# Relay_switcher.net
KiCad netlist of a schematic drawn in Altium Designer
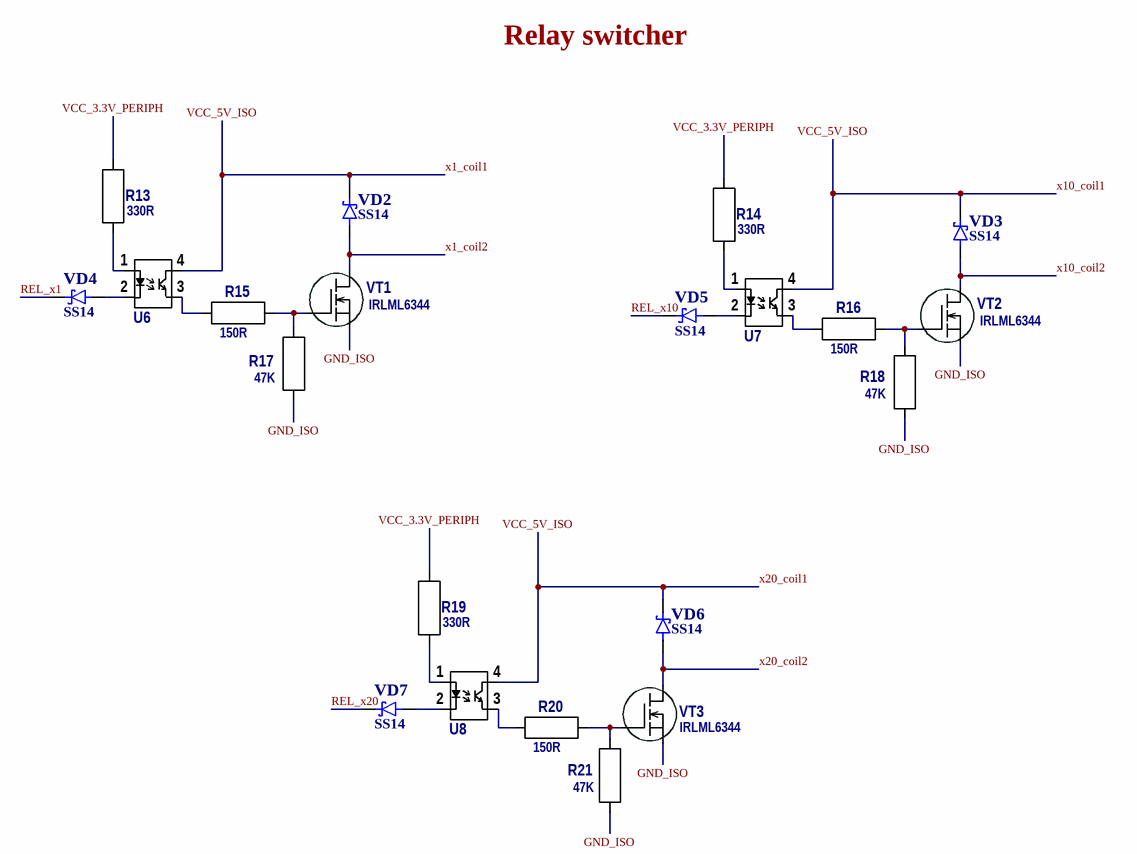
[diagram p0: Relay_switcher.SchDoc]

(export (version "E")
  (design (tool "Eeschema 10.0.6"))
  (components
    (comp (ref "R13") (value "330R") (footprint "Res_1206 3D") (libsource (lib "RLC V7.1_BVI") (part "R")))
    (comp (ref "R14") (value "330R") (footprint "Res_1206 3D") (libsource (lib "RLC V7.1_BVI") (part "R")))
    (comp (ref "R15") (value "150R") (footprint "Res_1206 3D") (libsource (lib "RLC V7.1_BVI") (part "R")))
    (comp (ref "R16") (value "150R") (footprint "Res_1206 3D") (libsource (lib "RLC V7.1_BVI") (part "R")))
    (comp (ref "R17") (value "47K") (footprint "Res_1206 3D") (libsource (lib "RLC V7.1_BVI") (part "R")))
    (comp (ref "R18") (value "47K") (footprint "Res_1206 3D") (libsource (lib "RLC V7.1_BVI") (part "R")))
    (comp (ref "R19") (value "330R") (footprint "Res_1206 3D") (libsource (lib "RLC V7.1_BVI") (part "R")))
    (comp (ref "R20") (value "150R") (footprint "Res_1206 3D") (libsource (lib "RLC V7.1_BVI") (part "R")))
    (comp (ref "R21") (value "47K") (footprint "Res_1206 3D") (libsource (lib "RLC V7.1_BVI") (part "R")))
    (comp (ref "U6")
      (value "Optocoupler EL817 DIP-4")
      (footprint "DIP-4")
      (description "Оптрон выход - транзистор")
      (libsource (lib "Optocoupler V2.2_BVI") (part "EL817"))
    )
    (comp (ref "U7")
      (value "Optocoupler EL817 DIP-4")
      (footprint "DIP-4")
      (description "Оптрон выход - транзистор")
      (libsource (lib "Optocoupler V2.2_BVI") (part "EL817"))
    )
    (comp (ref "U8")
      (value "Optocoupler EL817 DIP-4")
      (footprint "DIP-4")
      (description "Оптрон выход - транзистор")
      (libsource (lib "Optocoupler V2.2_BVI") (part "EL817"))
    )
    (comp (ref "VD2")
      (value "SS14")
      (footprint "SMA")
      (description "Diode Schottky 40 V 1A Surface Mount DO-214AC (SMA)")
      (fields (field (name "MF") "ON"))
      (libsource (lib "SS14") (part "SS14"))
    )
    (comp (ref "VD3")
      (value "SS14")
      (footprint "SMA")
      (description "Diode Schottky 40 V 1A Surface Mount DO-214AC (SMA)")
      (fields (field (name "MF") "ON"))
      (libsource (lib "SS14") (part "SS14"))
    )
    (comp (ref "VD4")
      (value "SS14")
      (footprint "SMA")
      (description "Diode Schottky 40 V 1A Surface Mount DO-214AC (SMA)")
      (fields (field (name "MF") "ON"))
      (libsource (lib "SS14") (part "SS14"))
    )
    (comp (ref "VD5")
      (value "SS14")
      (footprint "SMA")
      (description "Diode Schottky 40 V 1A Surface Mount DO-214AC (SMA)")
      (fields (field (name "MF") "ON"))
      (libsource (lib "SS14") (part "SS14"))
    )
    (comp (ref "VD6")
      (value "SS14")
      (footprint "SMA")
      (description "Diode Schottky 40 V 1A Surface Mount DO-214AC (SMA)")
      (fields (field (name "MF") "ON"))
      (libsource (lib "SS14") (part "SS14"))
    )
    (comp (ref "VD7")
      (value "SS14")
      (footprint "SMA")
      (description "Diode Schottky 40 V 1A Surface Mount DO-214AC (SMA)")
      (fields (field (name "MF") "ON"))
      (libsource (lib "SS14") (part "SS14"))
    )
    (comp (ref "VT1")
      (value "IRLML6344")
      (footprint "SOT-23-3")
      (description "Транзистор MOSFET N-канал IRLML6344")
      (libsource (lib "VD_VT_V6.3 BVI") (part "VT MOSFET-N"))
    )
    (comp (ref "VT2")
      (value "IRLML6344")
      (footprint "SOT-23-3")
      (description "Транзистор MOSFET N-канал IRLML6344")
      (libsource (lib "VD_VT_V6.3 BVI") (part "VT MOSFET-N"))
    )
    (comp (ref "VT3")
      (value "IRLML6344")
      (footprint "SOT-23-3")
      (description "Транзистор MOSFET N-канал IRLML6344")
      (libsource (lib "VD_VT_V6.3 BVI") (part "VT MOSFET-N"))
    )
  )
  (nets
    (net (code "1") (name "/GND_ISO") (class "Default")
      (node (ref "R17") (pin "2") (pintype "passive"))
      (node (ref "R18") (pin "2") (pintype "passive"))
      (node (ref "R21") (pin "2") (pintype "passive"))
      (node (ref "VT1") (pin "3") (pinfunction "S_3") (pintype "passive"))
      (node (ref "VT2") (pin "3") (pinfunction "S_3") (pintype "passive"))
      (node (ref "VT3") (pin "3") (pinfunction "S_3") (pintype "passive"))
    )
    (net (code "2") (name "/REL_x1") (class "Default")
      (node (ref "VD4") (pin "P2") (pinfunction "C_P2") (pintype "passive"))
    )
    (net (code "3") (name "/REL_x10") (class "Default")
      (node (ref "VD5") (pin "P2") (pinfunction "C_P2") (pintype "passive"))
    )
    (net (code "4") (name "/REL_x20") (class "Default")
      (node (ref "VD7") (pin "P2") (pinfunction "C_P2") (pintype "passive"))
    )
    (net (code "5") (name "/VCC_3.3V_PERIPH") (class "Default")
      (node (ref "R13") (pin "2") (pintype "passive"))
      (node (ref "R14") (pin "2") (pintype "passive"))
      (node (ref "R19") (pin "2") (pintype "passive"))
    )
    (net (code "6") (name "/VCC_5V_ISO") (class "Default")
      (node (ref "U6") (pin "4") (pinfunction "C_4") (pintype "passive"))
      (node (ref "U7") (pin "4") (pinfunction "C_4") (pintype "passive"))
      (node (ref "U8") (pin "4") (pinfunction "C_4") (pintype "passive"))
      (node (ref "VD2") (pin "P2") (pinfunction "C_P2") (pintype "passive"))
      (node (ref "VD3") (pin "P2") (pinfunction "C_P2") (pintype "passive"))
      (node (ref "VD6") (pin "P2") (pinfunction "C_P2") (pintype "passive"))
    )
    (net (code "7") (name "/x1_coil2") (class "Default")
      (node (ref "VD2") (pin "P1") (pinfunction "A_P1") (pintype "passive"))
      (node (ref "VT1") (pin "2") (pinfunction "D_2") (pintype "passive"))
    )
    (net (code "8") (name "/x10_coil2") (class "Default")
      (node (ref "VD3") (pin "P1") (pinfunction "A_P1") (pintype "passive"))
      (node (ref "VT2") (pin "2") (pinfunction "D_2") (pintype "passive"))
    )
    (net (code "9") (name "/x20_coil2") (class "Default")
      (node (ref "VD6") (pin "P1") (pinfunction "A_P1") (pintype "passive"))
      (node (ref "VT3") (pin "2") (pinfunction "D_2") (pintype "passive"))
    )
    (net (code "10") (name "Net-(U6-E)") (class "Default")
      (node (ref "R15") (pin "1") (pintype "passive"))
      (node (ref "U6") (pin "3") (pinfunction "E_3") (pintype "passive"))
    )
    (net (code "11") (name "Net-(U6-Led_A)") (class "Default")
      (node (ref "R13") (pin "1") (pintype "passive"))
      (node (ref "U6") (pin "1") (pinfunction "Led_A_1") (pintype "passive"))
    )
    (net (code "12") (name "Net-(U6-Led_C)") (class "Default")
      (node (ref "U6") (pin "2") (pinfunction "Led_C_2") (pintype "passive"))
      (node (ref "VD4") (pin "P1") (pinfunction "A_P1") (pintype "passive"))
    )
    (net (code "13") (name "Net-(U7-E)") (class "Default")
      (node (ref "R16") (pin "1") (pintype "passive"))
      (node (ref "U7") (pin "3") (pinfunction "E_3") (pintype "passive"))
    )
    (net (code "14") (name "Net-(U7-Led_A)") (class "Default")
      (node (ref "R14") (pin "1") (pintype "passive"))
      (node (ref "U7") (pin "1") (pinfunction "Led_A_1") (pintype "passive"))
    )
    (net (code "15") (name "Net-(U7-Led_C)") (class "Default")
      (node (ref "U7") (pin "2") (pinfunction "Led_C_2") (pintype "passive"))
      (node (ref "VD5") (pin "P1") (pinfunction "A_P1") (pintype "passive"))
    )
    (net (code "16") (name "Net-(U8-E)") (class "Default")
      (node (ref "R20") (pin "1") (pintype "passive"))
      (node (ref "U8") (pin "3") (pinfunction "E_3") (pintype "passive"))
    )
    (net (code "17") (name "Net-(U8-Led_A)") (class "Default")
      (node (ref "R19") (pin "1") (pintype "passive"))
      (node (ref "U8") (pin "1") (pinfunction "Led_A_1") (pintype "passive"))
    )
    (net (code "18") (name "Net-(U8-Led_C)") (class "Default")
      (node (ref "U8") (pin "2") (pinfunction "Led_C_2") (pintype "passive"))
      (node (ref "VD7") (pin "P1") (pinfunction "A_P1") (pintype "passive"))
    )
    (net (code "19") (name "Net-(VT1-G)") (class "Default")
      (node (ref "R15") (pin "2") (pintype "passive"))
      (node (ref "R17") (pin "1") (pintype "passive"))
      (node (ref "VT1") (pin "1") (pinfunction "G_1") (pintype "passive"))
    )
    (net (code "20") (name "Net-(VT2-G)") (class "Default")
      (node (ref "R16") (pin "2") (pintype "passive"))
      (node (ref "R18") (pin "1") (pintype "passive"))
      (node (ref "VT2") (pin "1") (pinfunction "G_1") (pintype "passive"))
    )
    (net (code "21") (name "Net-(VT3-G)") (class "Default")
      (node (ref "R20") (pin "2") (pintype "passive"))
      (node (ref "R21") (pin "1") (pintype "passive"))
      (node (ref "VT3") (pin "1") (pinfunction "G_1") (pintype "passive"))
    )
  )
)
